# op_amp.net
KiCad netlist of a schematic drawn in EAGLE
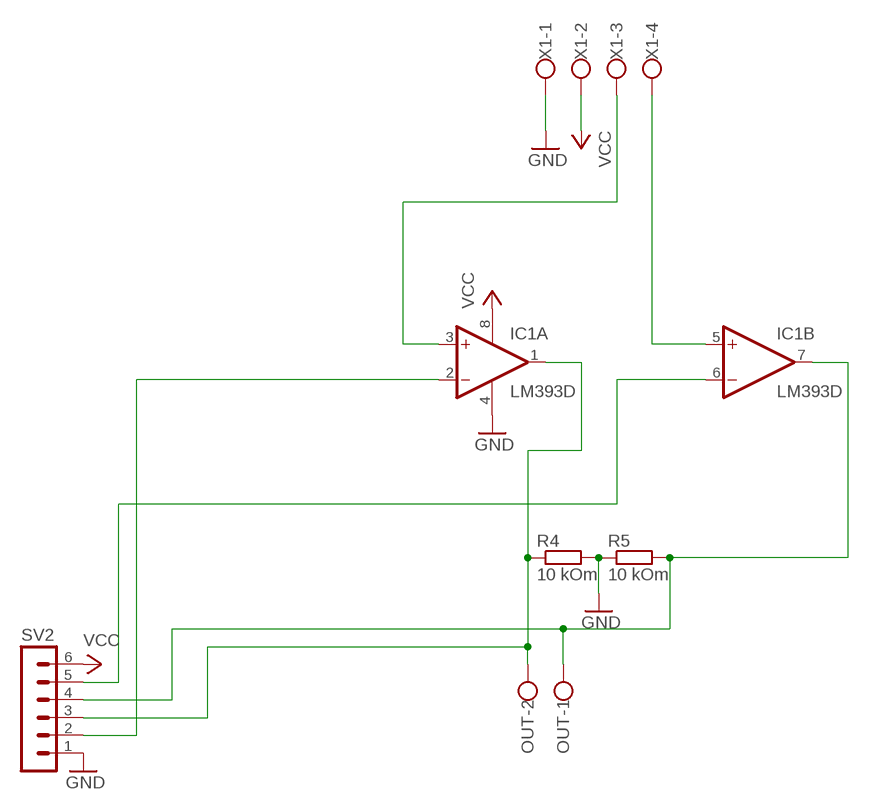
[diagram p0: schematic, sheet 1]
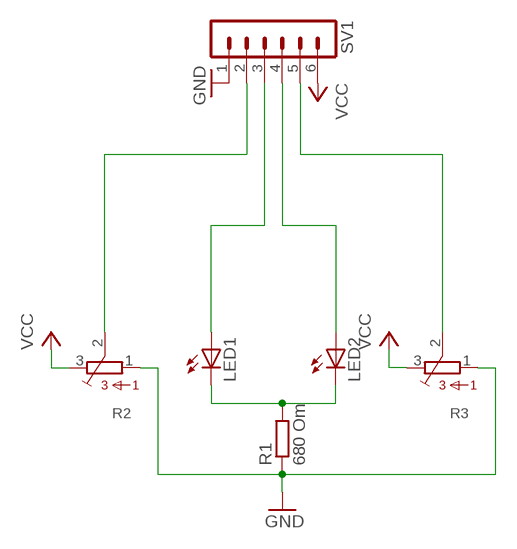
[diagram p1: schematic, sheet 2]

(export (version "E")
  (design (tool "Eeschema 10.0.6"))
  (components
    (comp (ref "LED1")
      (value "LED3MM")
      (footprint "eagle-import:LED3MM")
      (libsource (lib "eagle-import") (part "LED3MM"))
    )
    (comp (ref "LED2")
      (value "LED3MM")
      (footprint "eagle-import:LED3MM")
      (libsource (lib "eagle-import") (part "LED3MM"))
    )
    (comp (ref "R1")
      (value "680 Om")
      (footprint "eagle-import:0207_7")
      (libsource (lib "eagle-import") (part "R-EU_0207/7"))
    )
    (comp (ref "R2")
      (value "3362P")
      (footprint "eagle-import:3362P")
      (libsource (lib "eagle-import") (part "3362P"))
    )
    (comp (ref "R3")
      (value "3362P")
      (footprint "eagle-import:3362P")
      (libsource (lib "eagle-import") (part "3362P"))
    )
    (comp (ref "SV1")
      (value "MA06-1")
      (footprint "eagle-import:MA06-1")
      (libsource (lib "eagle-import") (part "MA06-1"))
    )
    (comp (ref "IC1")
      (value "LM393D")
      (footprint "eagle-import:SO08")
      (libsource (lib "eagle-import") (part "LM393D"))
    )
    (comp (ref "OUT")
      (value "W237-102")
      (footprint "eagle-import:W237-102")
      (fields (field (name "MPN") "237-102"))
      (libsource (lib "eagle-import") (part "W237-102"))
    )
    (comp (ref "R4")
      (value "10 kOm")
      (footprint "eagle-import:0207_7")
      (libsource (lib "eagle-import") (part "R-EU_0207/7"))
    )
    (comp (ref "R5")
      (value "10 kOm")
      (footprint "eagle-import:0207_7")
      (libsource (lib "eagle-import") (part "R-EU_0207/7"))
    )
    (comp (ref "SV2")
      (value "MA06-1")
      (footprint "eagle-import:MA06-1")
      (libsource (lib "eagle-import") (part "MA06-1"))
    )
    (comp (ref "X1")
      (value "W237-4")
      (footprint "eagle-import:W237-4")
      (libsource (lib "eagle-import") (part "W237-4"))
    )
  )
  (nets
    (net (code "1") (name "GND") (class "Default")
      (node (ref "IC1") (pin "4") (pinfunction "V-_4") (pintype "power_in"))
      (node (ref "R1") (pin "1") (pinfunction "1_1") (pintype "passive"))
      (node (ref "R2") (pin "1") (pinfunction "1_1") (pintype "passive"))
      (node (ref "R3") (pin "1") (pinfunction "1_1") (pintype "passive"))
      (node (ref "R4") (pin "2") (pinfunction "2_2") (pintype "passive"))
      (node (ref "R5") (pin "1") (pinfunction "1_1") (pintype "passive"))
      (node (ref "SV1") (pin "1") (pinfunction "1_1") (pintype "passive"))
      (node (ref "SV2") (pin "1") (pinfunction "1_1") (pintype "passive"))
      (node (ref "X1") (pin "1") (pinfunction "KL_1") (pintype "passive"))
    )
    (net (code "2") (name "Net-(IC1A-+IN)") (class "Default")
      (node (ref "IC1") (pin "3") (pinfunction "+IN_3") (pintype "input"))
      (node (ref "X1") (pin "3") (pinfunction "KL_3") (pintype "passive"))
    )
    (net (code "3") (name "Net-(IC1A--IN)") (class "Default")
      (node (ref "IC1") (pin "2") (pinfunction "-IN_2") (pintype "input"))
      (node (ref "SV2") (pin "2") (pinfunction "2_2") (pintype "passive"))
    )
    (net (code "4") (name "Net-(IC1A-OUT)") (class "Default")
      (node (ref "IC1") (pin "1") (pinfunction "OUT_1") (pintype "output"))
      (node (ref "OUT") (pin "2") (pinfunction "KL_2") (pintype "passive"))
      (node (ref "R4") (pin "1") (pinfunction "1_1") (pintype "passive"))
      (node (ref "SV2") (pin "3") (pinfunction "3_3") (pintype "passive"))
    )
    (net (code "5") (name "Net-(IC1B-+IN)") (class "Default")
      (node (ref "IC1") (pin "5") (pinfunction "+IN_5") (pintype "input"))
      (node (ref "X1") (pin "4") (pinfunction "KL_4") (pintype "passive"))
    )
    (net (code "6") (name "Net-(IC1B--IN)") (class "Default")
      (node (ref "IC1") (pin "6") (pinfunction "-IN_6") (pintype "input"))
      (node (ref "SV2") (pin "5") (pinfunction "5_5") (pintype "passive"))
    )
    (net (code "7") (name "Net-(IC1B-OUT)") (class "Default")
      (node (ref "IC1") (pin "7") (pinfunction "OUT_7") (pintype "output"))
      (node (ref "OUT") (pin "1") (pinfunction "KL_1") (pintype "passive"))
      (node (ref "R5") (pin "2") (pinfunction "2_2") (pintype "passive"))
      (node (ref "SV2") (pin "4") (pinfunction "4_4") (pintype "passive"))
    )
    (net (code "8") (name "Net-(LED1-C)") (class "Default")
      (node (ref "LED1") (pin "K") (pinfunction "C_K") (pintype "passive"))
      (node (ref "LED2") (pin "K") (pinfunction "C_K") (pintype "passive"))
      (node (ref "R1") (pin "2") (pinfunction "2_2") (pintype "passive"))
    )
    (net (code "9") (name "Net-(LED1-PadA)") (class "Default")
      (node (ref "LED1") (pin "A") (pinfunction "A_A") (pintype "passive"))
      (node (ref "SV1") (pin "3") (pinfunction "3_3") (pintype "passive"))
    )
    (net (code "10") (name "Net-(LED2-PadA)") (class "Default")
      (node (ref "LED2") (pin "A") (pinfunction "A_A") (pintype "passive"))
      (node (ref "SV1") (pin "4") (pinfunction "4_4") (pintype "passive"))
    )
    (net (code "11") (name "Net-(R2-Pad2)") (class "Default")
      (node (ref "R2") (pin "2") (pinfunction "2_2") (pintype "passive"))
      (node (ref "SV1") (pin "2") (pinfunction "2_2") (pintype "passive"))
    )
    (net (code "12") (name "Net-(R3-Pad2)") (class "Default")
      (node (ref "R3") (pin "2") (pinfunction "2_2") (pintype "passive"))
      (node (ref "SV1") (pin "5") (pinfunction "5_5") (pintype "passive"))
    )
    (net (code "13") (name "VCC") (class "Default")
      (node (ref "IC1") (pin "8") (pinfunction "V+_8") (pintype "power_in"))
      (node (ref "R2") (pin "3") (pinfunction "3_3") (pintype "passive"))
      (node (ref "R3") (pin "3") (pinfunction "3_3") (pintype "passive"))
      (node (ref "SV1") (pin "6") (pinfunction "6_6") (pintype "passive"))
      (node (ref "SV2") (pin "6") (pinfunction "6_6") (pintype "passive"))
      (node (ref "X1") (pin "2") (pinfunction "KL_2") (pintype "passive"))
    )
  )
)
